# CoffeePal.net
KiCad netlist of a schematic drawn in EAGLE
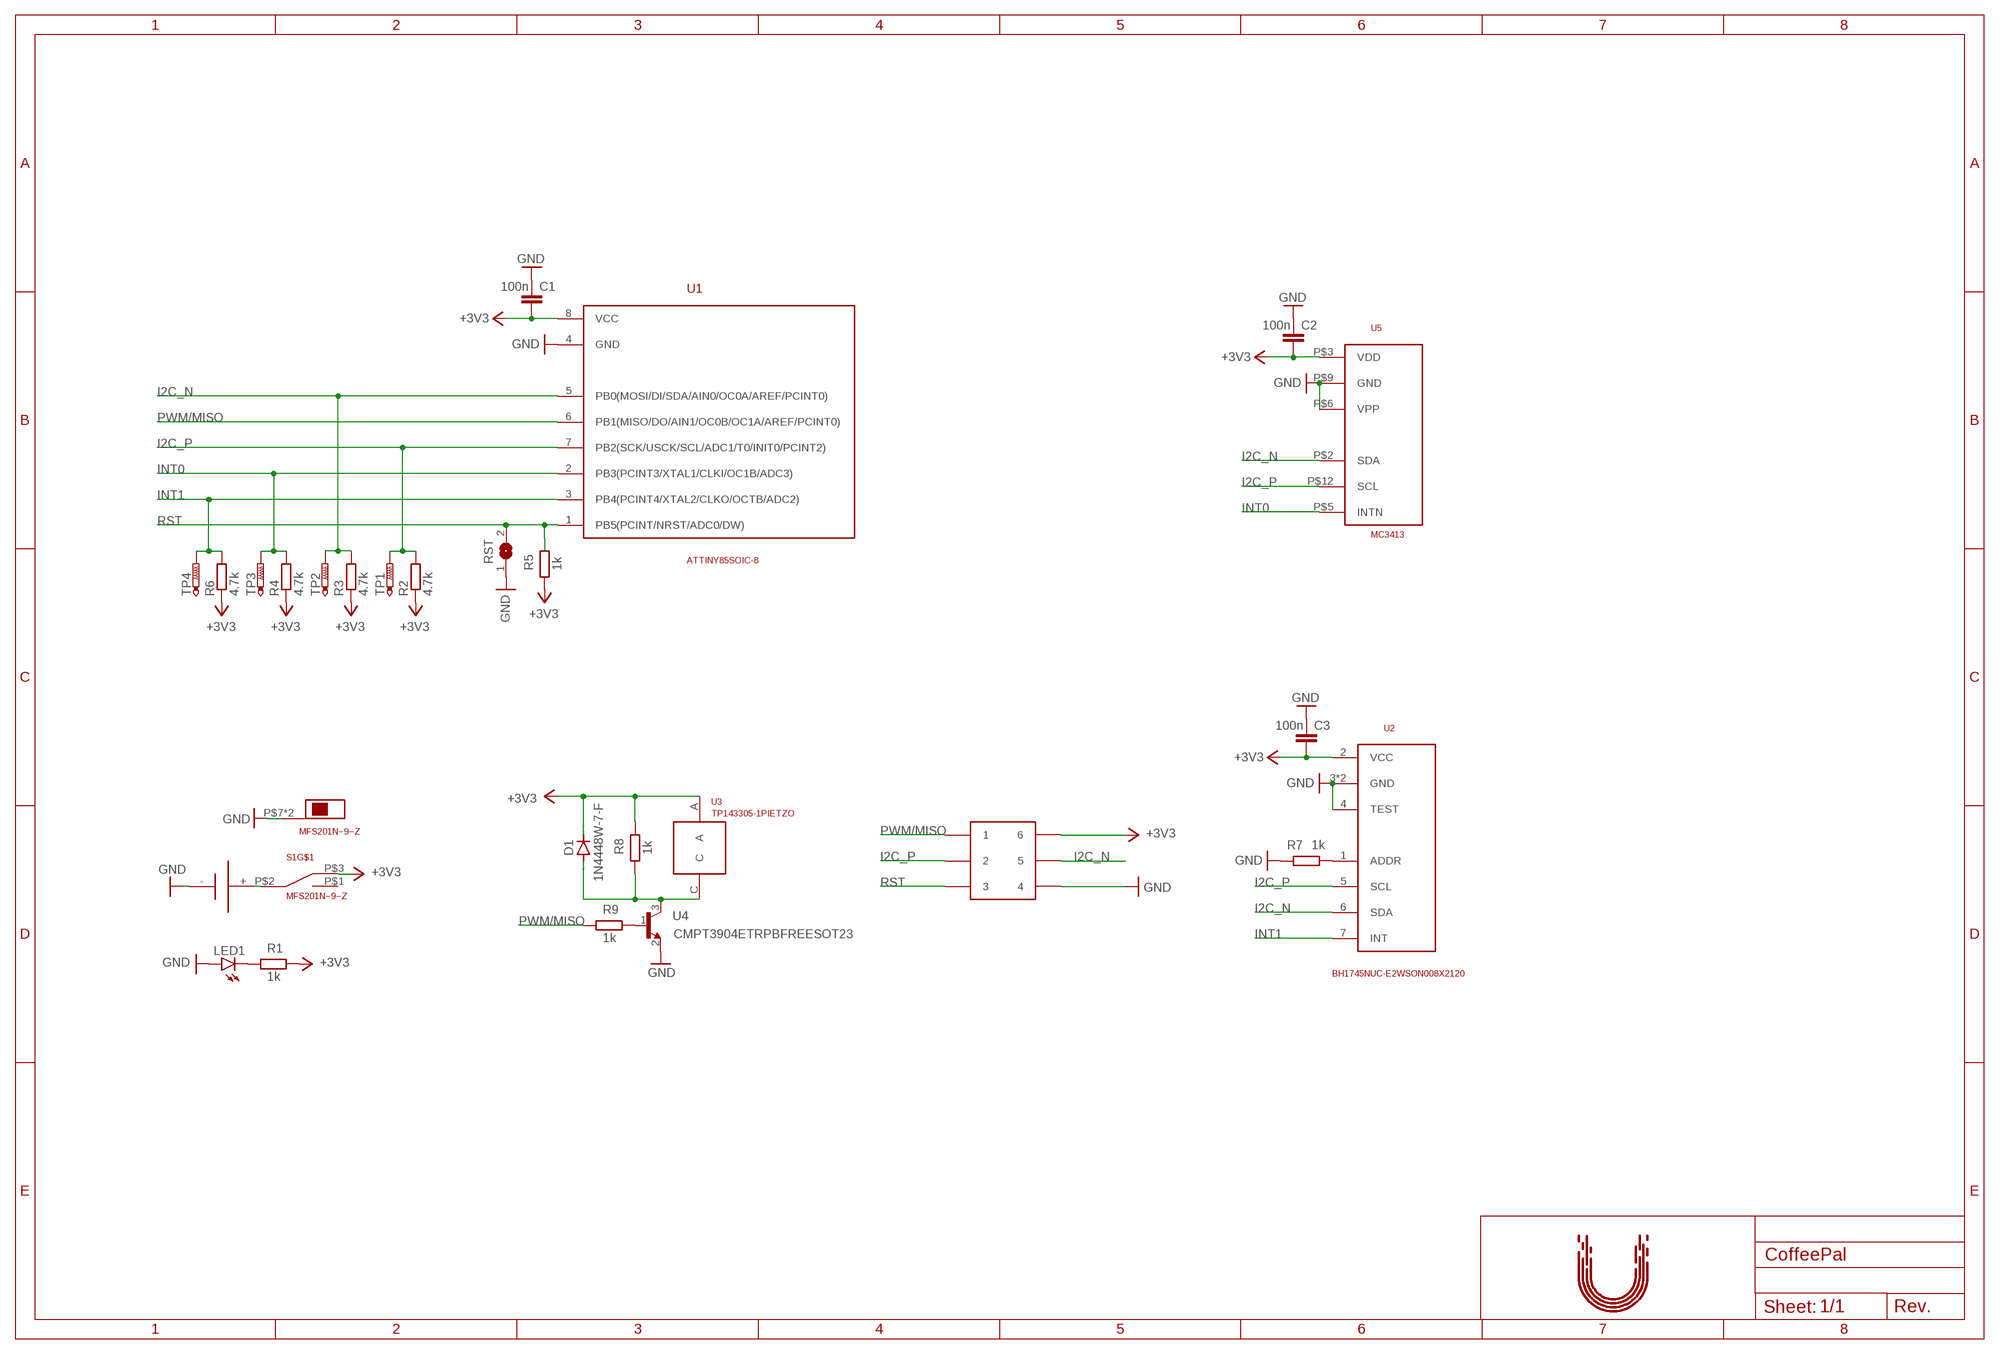
[diagram p0: schematic, sheet 1]

(export (version "E")
  (design (tool "Eeschema 10.0.6"))
  (components
    (comp (ref "C1")
      (value "100n")
      (footprint "eagle-import:0603")
      (libsource (lib "eagle-import") (part "CAPACITORC-0603"))
    )
    (comp (ref "C2")
      (value "100n")
      (footprint "eagle-import:0603")
      (libsource (lib "eagle-import") (part "CAPACITORC-0603"))
    )
    (comp (ref "C3")
      (value "100n")
      (footprint "eagle-import:0603")
      (libsource (lib "eagle-import") (part "CAPACITORC-0603"))
    )
    (comp (ref "D1")
      (value "1N4448W-7-F")
      (footprint "eagle-import:SOD-123_MINI-SMA")
      (libsource (lib "eagle-import") (part "DIODE1"))
    )
    (comp (ref "LED1")
      (value "LEDLED_1206")
      (footprint "eagle-import:DIOC3216X75N")
      (libsource (lib "eagle-import") (part "LEDLED_1206"))
    )
    (comp (ref "PROGRAM")
      (value "3X2_PINHEADER3X2_PINHEADER")
      (footprint "eagle-import:HDRV6W64P254_2X3_900X508X838B")
      (fields (field (name "MPN") "5-146258-3"))
      (libsource (lib "eagle-import") (part "3X2_PINHEADER3X2_PINHEADER"))
    )
    (comp (ref "R1")
      (value "1k")
      (footprint "eagle-import:R0603")
      (libsource (lib "eagle-import") (part "RESISTOR"))
    )
    (comp (ref "R2")
      (value "4.7k")
      (footprint "eagle-import:R0603")
      (libsource (lib "eagle-import") (part "RESISTOR"))
    )
    (comp (ref "R3")
      (value "4.7k")
      (footprint "eagle-import:R0603")
      (libsource (lib "eagle-import") (part "RESISTOR"))
    )
    (comp (ref "R4")
      (value "4.7k")
      (footprint "eagle-import:R0603")
      (libsource (lib "eagle-import") (part "RESISTOR"))
    )
    (comp (ref "R5")
      (value "1k")
      (footprint "eagle-import:R0603")
      (libsource (lib "eagle-import") (part "RESISTOR"))
    )
    (comp (ref "R6")
      (value "4.7k")
      (footprint "eagle-import:R0603")
      (libsource (lib "eagle-import") (part "RESISTOR"))
    )
    (comp (ref "R7")
      (value "1k")
      (footprint "eagle-import:R0603")
      (libsource (lib "eagle-import") (part "RESISTOR"))
    )
    (comp (ref "R8")
      (value "1k")
      (footprint "eagle-import:R0603")
      (libsource (lib "eagle-import") (part "RESISTOR"))
    )
    (comp (ref "R9")
      (value "1k")
      (footprint "eagle-import:R0603")
      (libsource (lib "eagle-import") (part "RESISTOR"))
    )
    (comp (ref "RST")
      (value "JUMPER")
      (footprint "eagle-import:SJ")
      (libsource (lib "eagle-import") (part "JUMPER"))
    )
    (comp (ref "S1")
      (value "MFS201N−9−Z")
      (footprint "eagle-import:MFS201N-9-Z")
      (libsource (lib "eagle-import") (part "MFS201N−9−Z"))
    )
    (comp (ref "TP1")
      (value "PTR1B1,27")
      (footprint "eagle-import:B1,27")
      (libsource (lib "eagle-import") (part "PTR1B1,27"))
    )
    (comp (ref "TP2")
      (value "PTR1B1,27")
      (footprint "eagle-import:B1,27")
      (libsource (lib "eagle-import") (part "PTR1B1,27"))
    )
    (comp (ref "TP3")
      (value "PTR1B1,27")
      (footprint "eagle-import:B1,27")
      (libsource (lib "eagle-import") (part "PTR1B1,27"))
    )
    (comp (ref "TP4")
      (value "PTR1B1,27")
      (footprint "eagle-import:B1,27")
      (libsource (lib "eagle-import") (part "PTR1B1,27"))
    )
    (comp (ref "U$2")
      (value "1061TR")
      (footprint "eagle-import:1061TR")
      (libsource (lib "eagle-import") (part "1061TR"))
    )
    (comp (ref "U$3")
      (value "UTBULT_DESIGN1")
      (footprint "eagle-import:UD_1")
      (libsource (lib "eagle-import") (part "UTBULT_DESIGN1"))
    )
    (comp (ref "U1")
      (value "ATTINY85SOIC-8")
      (footprint "eagle-import:SOIC127P798X216-8N")
      (fields (field (name "MPN") "ATTINY85V-10SUR"))
      (libsource (lib "eagle-import") (part "ATTINY85SOIC-8"))
    )
    (comp (ref "U2")
      (value "BH1745NUC-E2WSON008X2120")
      (footprint "eagle-import:SON50P210X200X60-9T75X150N")
      (fields (field (name "MPN") "BH1745NUC-E2"))
      (libsource (lib "eagle-import") (part "BH1745NUC-E2WSON008X2120"))
    )
    (comp (ref "U3")
      (value "TP143305-1PIETZO")
      (footprint "eagle-import:SODFL151143X1070N")
      (fields (field (name "MPN") "TP143305-1"))
      (libsource (lib "eagle-import") (part "TP143305-1PIETZO"))
    )
    (comp (ref "U4")
      (value "CMPT3904ETRPBFREESOT23")
      (footprint "eagle-import:SOT95P240X110-3N")
      (fields (field (name "MPN") "CMPT3904E TR PBFREE "))
      (libsource (lib "eagle-import") (part "CMPT3904ETRPBFREESOT23"))
    )
    (comp (ref "U5")
      (value "MC3413")
      (footprint "eagle-import:VLGA-12")
      (libsource (lib "eagle-import") (part "MC3413"))
    )
  )
  (nets
    (net (code "1") (name "+3V3") (class "Default")
      (node (ref "C1") (pin "2") (pinfunction "2_2") (pintype "passive"))
      (node (ref "C2") (pin "2") (pinfunction "2_2") (pintype "passive"))
      (node (ref "C3") (pin "2") (pinfunction "2_2") (pintype "passive"))
      (node (ref "D1") (pin "C") (pinfunction "C_C") (pintype "passive"))
      (node (ref "PROGRAM") (pin "6") (pinfunction "6_6") (pintype "bidirectional"))
      (node (ref "R1") (pin "2") (pinfunction "2_2") (pintype "passive"))
      (node (ref "R2") (pin "1") (pinfunction "1_1") (pintype "passive"))
      (node (ref "R3") (pin "1") (pinfunction "1_1") (pintype "passive"))
      (node (ref "R4") (pin "1") (pinfunction "1_1") (pintype "passive"))
      (node (ref "R5") (pin "1") (pinfunction "1_1") (pintype "passive"))
      (node (ref "R6") (pin "1") (pinfunction "1_1") (pintype "passive"))
      (node (ref "R8") (pin "2") (pinfunction "2_2") (pintype "passive"))
      (node (ref "S1") (pin "P$3") (pinfunction "P$3_P$3") (pintype "bidirectional"))
      (node (ref "U1") (pin "8") (pinfunction "VCC_8") (pintype "power_in"))
      (node (ref "U2") (pin "2") (pinfunction "VCC_2") (pintype "power_in"))
      (node (ref "U3") (pin "A") (pinfunction "A_A") (pintype "input"))
      (node (ref "U5") (pin "P$3") (pinfunction "VDD_P$3") (pintype "power_in"))
    )
    (net (code "2") (name "/I2C_N") (class "Default")
      (node (ref "PROGRAM") (pin "5") (pinfunction "5_5") (pintype "bidirectional"))
      (node (ref "R3") (pin "2") (pinfunction "2_2") (pintype "passive"))
      (node (ref "TP2") (pin "TP") (pinfunction "TP_TP") (pintype "input"))
      (node (ref "U1") (pin "5") (pinfunction "PB0(MOSI/DI/SDA/AIN0/OC0A/AREF/PCINT0)_5") (pintype "bidirectional"))
      (node (ref "U2") (pin "6") (pinfunction "SDA_6") (pintype "bidirectional"))
      (node (ref "U5") (pin "P$2") (pinfunction "SDA_P$2") (pintype "bidirectional"))
    )
    (net (code "3") (name "/I2C_P") (class "Default")
      (node (ref "PROGRAM") (pin "2") (pinfunction "2_2") (pintype "bidirectional"))
      (node (ref "R2") (pin "2") (pinfunction "2_2") (pintype "passive"))
      (node (ref "TP1") (pin "TP") (pinfunction "TP_TP") (pintype "input"))
      (node (ref "U1") (pin "7") (pinfunction "PB2(SCK/USCK/SCL/ADC1/T0/INIT0/PCINT2)_7") (pintype "bidirectional"))
      (node (ref "U2") (pin "5") (pinfunction "SCL_5") (pintype "input"))
      (node (ref "U5") (pin "P$12") (pinfunction "SCL_P$12") (pintype "input"))
    )
    (net (code "4") (name "/INT0") (class "Default")
      (node (ref "R4") (pin "2") (pinfunction "2_2") (pintype "passive"))
      (node (ref "TP3") (pin "TP") (pinfunction "TP_TP") (pintype "input"))
      (node (ref "U1") (pin "2") (pinfunction "PB3(PCINT3/XTAL1/CLKI/OC1B/ADC3)_2") (pintype "bidirectional"))
      (node (ref "U5") (pin "P$5") (pinfunction "INTN_P$5") (pintype "output"))
    )
    (net (code "5") (name "/INT1") (class "Default")
      (node (ref "R6") (pin "2") (pinfunction "2_2") (pintype "passive"))
      (node (ref "TP4") (pin "TP") (pinfunction "TP_TP") (pintype "input"))
      (node (ref "U1") (pin "3") (pinfunction "PB4(PCINT4/XTAL2/CLKO/OCTB/ADC2)_3") (pintype "bidirectional"))
      (node (ref "U2") (pin "7") (pinfunction "INT_7") (pintype "output"))
    )
    (net (code "6") (name "/PWM{slash}MISO") (class "Default")
      (node (ref "PROGRAM") (pin "1") (pinfunction "1_1") (pintype "bidirectional"))
      (node (ref "R9") (pin "1") (pinfunction "1_1") (pintype "passive"))
      (node (ref "U1") (pin "6") (pinfunction "PB1(MISO/DO/AIN1/OC0B/OC1A/AREF/PCINT0)_6") (pintype "bidirectional"))
    )
    (net (code "7") (name "/RST") (class "Default")
      (node (ref "PROGRAM") (pin "3") (pinfunction "3_3") (pintype "bidirectional"))
      (node (ref "R5") (pin "2") (pinfunction "2_2") (pintype "passive"))
      (node (ref "RST") (pin "2") (pinfunction "2_2") (pintype "passive"))
      (node (ref "U1") (pin "1") (pinfunction "PB5(PCINT/NRST/ADC0/DW)_1") (pintype "bidirectional"))
    )
    (net (code "8") (name "GND") (class "Default")
      (node (ref "C1") (pin "1") (pinfunction "1_1") (pintype "passive"))
      (node (ref "C2") (pin "1") (pinfunction "1_1") (pintype "passive"))
      (node (ref "C3") (pin "1") (pinfunction "1_1") (pintype "passive"))
      (node (ref "LED1") (pin "A") (pinfunction "A_A") (pintype "passive"))
      (node (ref "PROGRAM") (pin "4") (pinfunction "4_4") (pintype "bidirectional"))
      (node (ref "R7") (pin "1") (pinfunction "1_1") (pintype "passive"))
      (node (ref "RST") (pin "1") (pinfunction "1_1") (pintype "passive"))
      (node (ref "S1") (pin "P$7") (pinfunction "P$1_P$7") (pintype "power_in"))
      (node (ref "S1") (pin "P$8") (pinfunction "P$1_P$8") (pintype "power_in"))
      (node (ref "U$2") (pin "-") (pinfunction "P$2_-") (pintype "power_in"))
      (node (ref "U1") (pin "4") (pinfunction "GND_4") (pintype "power_in"))
      (node (ref "U2") (pin "3") (pinfunction "GND_3") (pintype "power_in"))
      (node (ref "U2") (pin "4") (pinfunction "TEST_4") (pintype "input"))
      (node (ref "U2") (pin "9") (pinfunction "GND_9") (pintype "power_in"))
      (node (ref "U4") (pin "2") (pinfunction "E_2") (pintype "passive"))
      (node (ref "U5") (pin "P$6") (pinfunction "VPP_P$6") (pintype "input"))
      (node (ref "U5") (pin "P$9") (pinfunction "GND_P$9") (pintype "power_in"))
    )
    (net (code "9") (name "Net-(LED1-PadC)") (class "Default")
      (node (ref "LED1") (pin "C") (pinfunction "C_C") (pintype "passive"))
      (node (ref "R1") (pin "1") (pinfunction "1_1") (pintype "passive"))
    )
    (net (code "10") (name "Net-(U$2-P$1)") (class "Default")
      (node (ref "S1") (pin "P$2") (pinfunction "P$2_P$2") (pintype "bidirectional"))
      (node (ref "U$2") (pin "+") (pinfunction "P$1_+") (pintype "power_in"))
    )
    (net (code "11") (name "Net-(U2-ADDR)") (class "Default")
      (node (ref "R7") (pin "2") (pinfunction "2_2") (pintype "passive"))
      (node (ref "U2") (pin "1") (pinfunction "ADDR_1") (pintype "input"))
    )
    (net (code "12") (name "Net-(U4-B)") (class "Default")
      (node (ref "R9") (pin "2") (pinfunction "2_2") (pintype "passive"))
      (node (ref "U4") (pin "1") (pinfunction "B_1") (pintype "passive"))
    )
    (net (code "13") (name "Net-(U4-C)") (class "Default")
      (node (ref "D1") (pin "A") (pinfunction "A_A") (pintype "passive"))
      (node (ref "R8") (pin "1") (pinfunction "1_1") (pintype "passive"))
      (node (ref "U3") (pin "C") (pinfunction "C_C") (pintype "power_in"))
      (node (ref "U4") (pin "3") (pinfunction "C_3") (pintype "passive"))
    )
    (net (code "14") (name "unconnected-(S1-PadP$1)") (class "Default")
      (node (ref "S1") (pin "P$1") (pinfunction "P$1_P$1") (pintype "bidirectional"))
    )
  )
)
